# 2.net
KiCad netlist of a schematic drawn in Altium Designer
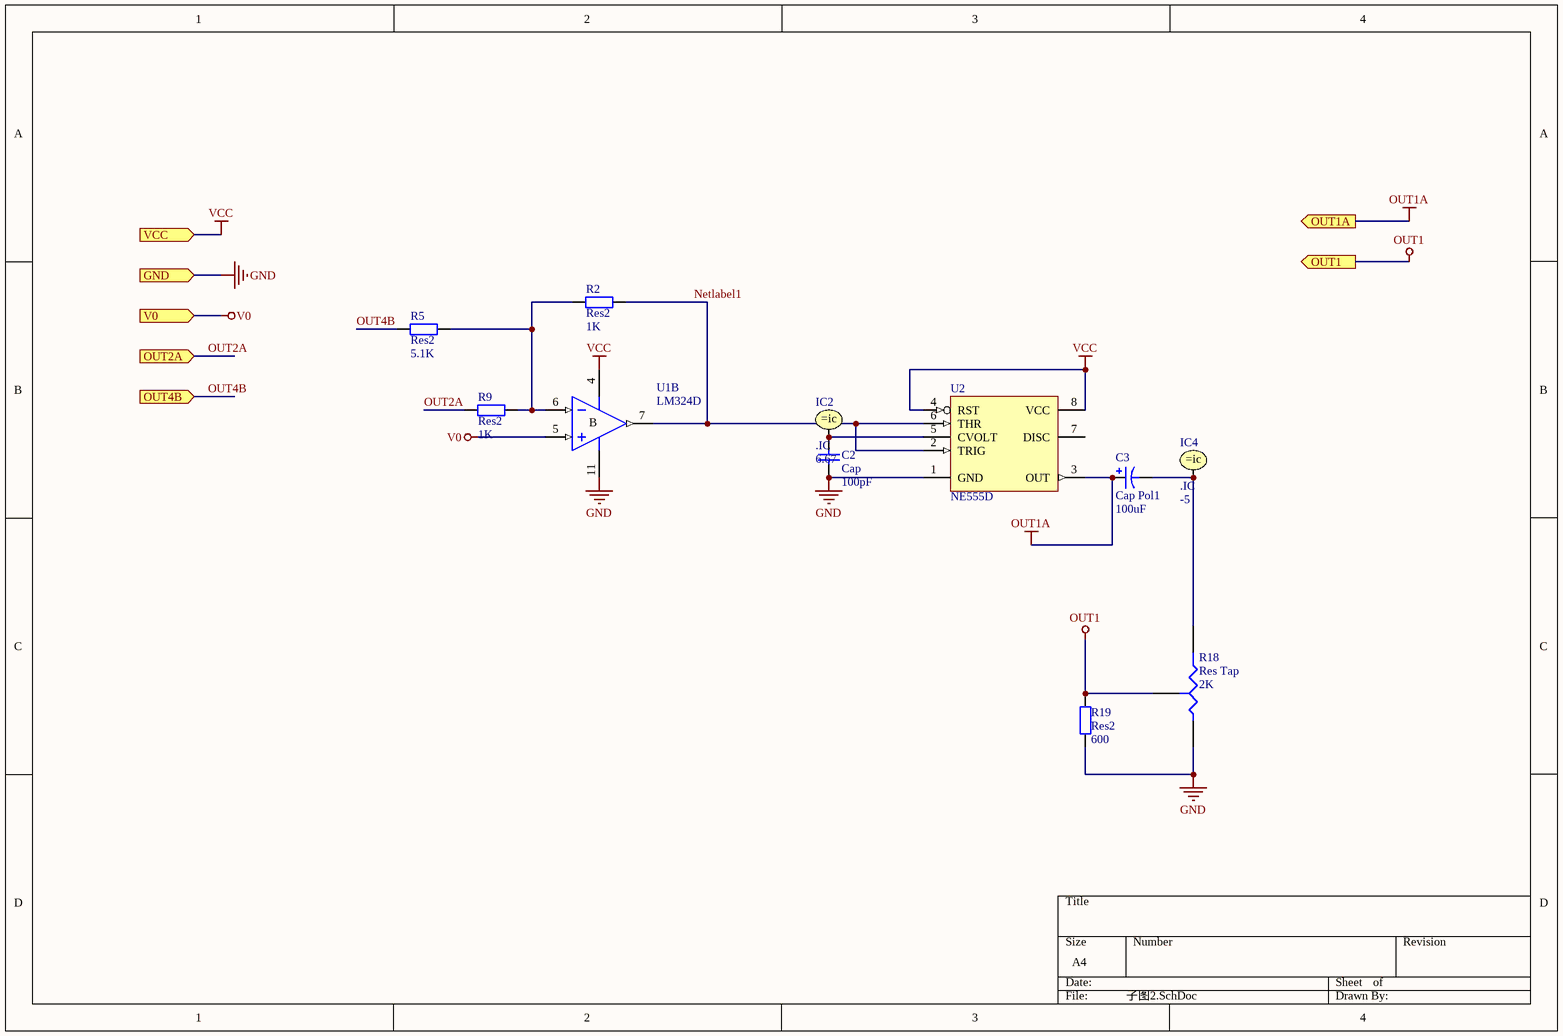
[diagram p0: 子图2.SchDoc]

(export (version "E")
  (design (tool "Eeschema 10.0.6"))
  (components
    (comp (ref "C2")
      (value "Cap")
      (footprint "LC-0805_C")
      (description "Capacitor")
      (fields (field (name "ALTIUM_VALUE") "100pF") (field (name "PUBLISHER") "Altium Limited"))
      (libsource (lib "Miscellaneous Devices") (part "Cap"))
    )
    (comp (ref "C3")
      (value "Cap Pol1")
      (footprint "LC-CASE-C_6032")
      (description "Polarized Capacitor (Radial)")
      (fields (field (name "ALTIUM_VALUE") "100uF") (field (name "PUBLISHER") "Altium Limited"))
      (libsource (lib "Miscellaneous Devices") (part "Cap Pol1"))
    )
    (comp (ref "IC2")
      (value ".IC")
      (description "Initial Condition")
      (fields (field (name "INITIAL VOLTAGE") "6.67") (field (name "PUBLISHER") "Altium Limited"))
      (libsource (lib "Simulation Sources") (part ".IC"))
    )
    (comp (ref "IC4")
      (value ".IC")
      (description "Initial Condition")
      (fields (field (name "INITIAL VOLTAGE") "-5") (field (name "PUBLISHER") "Altium Limited"))
      (libsource (lib "Simulation Sources") (part ".IC"))
    )
    (comp (ref "R2")
      (value "Res2")
      (footprint "LC-0805_R")
      (description "Resistor")
      (fields (field (name "ALTIUM_VALUE") "1K") (field (name "PUBLISHER") "Altium Limited"))
      (libsource (lib "Miscellaneous Devices") (part "Res2"))
    )
    (comp (ref "R5")
      (value "Res2")
      (footprint "LC-0805_R")
      (description "Resistor")
      (fields (field (name "ALTIUM_VALUE") "5.1K") (field (name "PUBLISHER") "Altium Limited"))
      (libsource (lib "Miscellaneous Devices") (part "Res2"))
    )
    (comp (ref "R9")
      (value "Res2")
      (footprint "LC-0805_R")
      (description "Resistor")
      (fields (field (name "ALTIUM_VALUE") "1K") (field (name "PUBLISHER") "Altium Limited"))
      (libsource (lib "Miscellaneous Devices") (part "Res2"))
    )
    (comp (ref "R18")
      (value "Res Tap")
      (footprint "电位器")
      (description "Tapped Resistor")
      (fields (field (name "ALTIUM_VALUE") "2K") (field (name "PUBLISHER") "Altium Limited"))
      (libsource (lib "Miscellaneous Devices") (part "Res Tap"))
    )
    (comp (ref "R19")
      (value "Res2")
      (footprint "LC-0805_R")
      (description "Resistor")
      (fields (field (name "ALTIUM_VALUE") "600") (field (name "PUBLISHER") "Altium Limited"))
      (libsource (lib "") (part "Res2_1"))
    )
    (comp (ref "U1")
      (value "LM324D")
      (footprint "SO14_N")
      (description "Low-Power Quad Operational Amplifier")
      (fields (field (name "PUBLISHER") "Altium Limited"))
      (libsource (lib "ST Operational Amplifier") (part "LM324D"))
    )
    (comp (ref "U2")
      (value "NE555D")
      (footprint "D008_N")
      (description "Precision Timer")
      (fields (field (name "PUBLISHER") "Altium Limited"))
      (libsource (lib "TI Analog Timer Circuit") (part "NE555D"))
    )
  )
  (nets
    (net (code "1") (name "/Netlabel1") (class "Default")
      (node (ref "R2") (pin "2") (pinfunction "2_2") (pintype "passive"))
      (node (ref "U1") (pin "7") (pinfunction "OUT_7") (pintype "output"))
      (node (ref "U2") (pin "2") (pinfunction "TRIG_2") (pintype "input"))
      (node (ref "U2") (pin "6") (pinfunction "THR_6") (pintype "input"))
    )
    (net (code "2") (name "/OUT2A") (class "Default")
      (node (ref "R9") (pin "1") (pinfunction "1_1") (pintype "passive"))
    )
    (net (code "3") (name "/OUT4B") (class "Default")
      (node (ref "R5") (pin "1") (pinfunction "1_1") (pintype "passive"))
    )
    (net (code "4") (name "GND") (class "Default")
      (node (ref "C2") (pin "1") (pinfunction "1_1") (pintype "passive"))
      (node (ref "R18") (pin "1") (pinfunction "A_1") (pintype "passive"))
      (node (ref "R19") (pin "1") (pinfunction "1_1") (pintype "passive"))
      (node (ref "U1") (pin "11") (pinfunction "V-_11") (pintype "power_in"))
      (node (ref "U2") (pin "1") (pinfunction "GND_1") (pintype "power_in"))
    )
    (net (code "5") (name "Net-(R18-B)") (class "Default")
      (node (ref "C3") (pin "2") (pinfunction "2_2") (pintype "passive"))
      (node (ref "IC4") (pin "1") (pinfunction "1_1") (pintype "passive"))
      (node (ref "R18") (pin "2") (pinfunction "B_2") (pintype "passive"))
    )
    (net (code "6") (name "Net-(U1B-IN-)") (class "Default")
      (node (ref "R2") (pin "1") (pinfunction "1_1") (pintype "passive"))
      (node (ref "R5") (pin "2") (pinfunction "2_2") (pintype "passive"))
      (node (ref "R9") (pin "2") (pinfunction "2_2") (pintype "passive"))
      (node (ref "U1") (pin "6") (pinfunction "IN-_6") (pintype "input"))
    )
    (net (code "7") (name "Net-(U2-CVOLT)") (class "Default")
      (node (ref "C2") (pin "2") (pinfunction "2_2") (pintype "passive"))
      (node (ref "IC2") (pin "1") (pinfunction "1_1") (pintype "passive"))
      (node (ref "U2") (pin "5") (pinfunction "CVOLT_5") (pintype "passive"))
    )
    (net (code "8") (name "OUT1") (class "Default")
      (node (ref "R18") (pin "3") (pinfunction "TAP_3") (pintype "passive"))
      (node (ref "R19") (pin "2") (pinfunction "2_2") (pintype "passive"))
    )
    (net (code "9") (name "OUT1A") (class "Default")
      (node (ref "C3") (pin "1") (pinfunction "1_1") (pintype "passive"))
      (node (ref "U2") (pin "3") (pinfunction "OUT_3") (pintype "output"))
    )
    (net (code "10") (name "V0") (class "Default")
      (node (ref "U1") (pin "5") (pinfunction "IN+_5") (pintype "input"))
    )
    (net (code "11") (name "VCC") (class "Default")
      (node (ref "U1") (pin "4") (pinfunction "V+_4") (pintype "power_in"))
      (node (ref "U2") (pin "4") (pinfunction "RST_4") (pintype "input"))
      (node (ref "U2") (pin "8") (pinfunction "VCC_8") (pintype "power_in"))
    )
    (net (code "12") (name "unconnected-(U2-DISC-Pad7)") (class "Default")
      (node (ref "U2") (pin "7") (pinfunction "DISC_7") (pintype "open_collector"))
    )
  )
)
